# Review_PCD_1_1.net
KiCad netlist of a schematic drawn in EAGLE
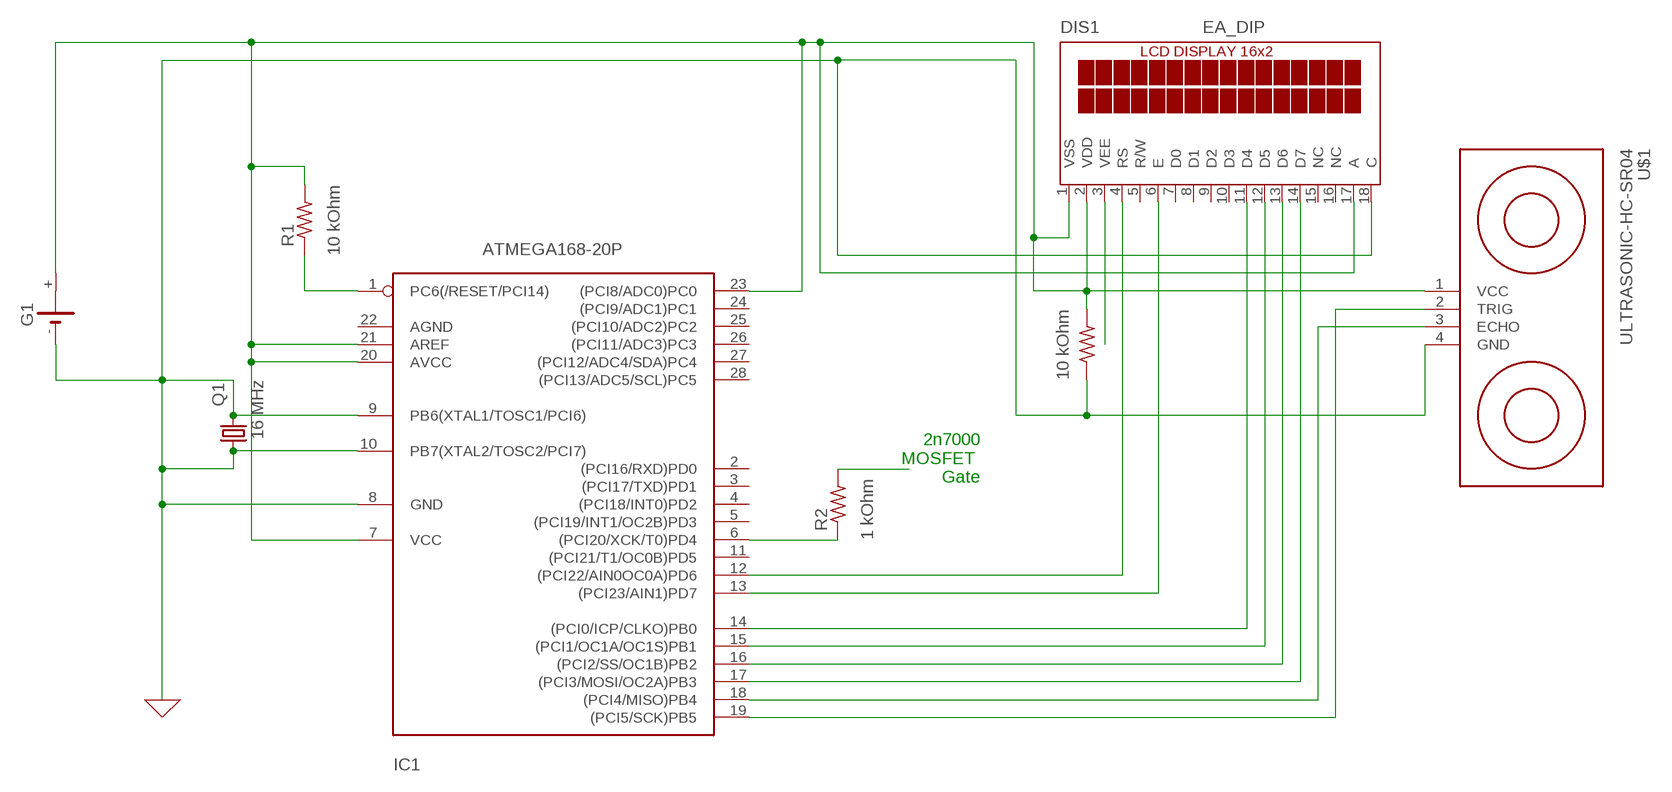
[diagram p0: schematic, sheet 1]

(export (version "E")
  (design (tool "Eeschema 10.0.6"))
  (components
    (comp (ref "DIS1")
      (value "EA_DIP")
      (footprint "eagle-import:EA_DIP")
      (libsource (lib "eagle-import") (part "EA_DIP"))
    )
    (comp (ref "G1")
      (value "CR1/2")
      (footprint "eagle-import:CR1_2")
      (libsource (lib "eagle-import") (part "CR1/2"))
    )
    (comp (ref "IC1")
      (value "ATMEGA168-20P")
      (footprint "eagle-import:DIL28-3")
      (libsource (lib "eagle-import") (part "ATMEGA168P-20"))
    )
    (comp (ref "Q1")
      (value "KX-4")
      (footprint "eagle-import:1.6X1.2")
      (fields (field (name "Q1") "16 MHz"))
      (libsource (lib "eagle-import") (part "KX-4"))
    )
    (comp (ref "R1")
      (value "R-US_R2012W")
      (footprint "eagle-import:R2012W")
      (fields (field (name "R1") "10 kOhm"))
      (libsource (lib "eagle-import") (part "R-US_R2012W"))
    )
    (comp (ref "R2")
      (value "R-US_R2012W")
      (footprint "eagle-import:R2012W")
      (fields (field (name "R1") "1 kOhm"))
      (libsource (lib "eagle-import") (part "R-US_R2012W"))
    )
    (comp (ref "R3")
      (value "R-US_R2012W")
      (footprint "eagle-import:R2012W")
      (fields (field (name "R1") "10 kOhm"))
      (libsource (lib "eagle-import") (part "R-US_R2012W"))
    )
    (comp (ref "U$1")
      (value "ULTRASONIC-HC-SR04")
      (footprint "eagle-import:ULTRASONIC-HC-SR04")
      (libsource (lib "eagle-import") (part "ULTRASONIC-HC-SR04"))
    )
  )
  (nets
    (net (code "1") (name "GND") (class "Default")
      (node (ref "DIS1") (pin "18") (pinfunction "C_18") (pintype "passive"))
      (node (ref "G1") (pin "-") (pinfunction "-_-") (pintype "passive"))
      (node (ref "IC1") (pin "10") (pinfunction "PB7(XTAL2/TOSC2/PCI7)_10") (pintype "bidirectional"))
      (node (ref "IC1") (pin "8") (pinfunction "GND_8") (pintype "bidirectional"))
      (node (ref "IC1") (pin "9") (pinfunction "PB6(XTAL1/TOSC1/PCI6)_9") (pintype "bidirectional"))
      (node (ref "Q1") (pin "1") (pinfunction "1_1") (pintype "passive"))
      (node (ref "Q1") (pin "3") (pinfunction "2_3") (pintype "passive"))
      (node (ref "R3") (pin "1") (pinfunction "1_1") (pintype "passive"))
      (node (ref "U$1") (pin "4") (pinfunction "GND_4") (pintype "power_in"))
    )
    (net (code "2") (name "Net-(DIS1-A)") (class "Default")
      (node (ref "DIS1") (pin "1") (pinfunction "VSS_1") (pintype "power_in"))
      (node (ref "DIS1") (pin "17") (pinfunction "A_17") (pintype "passive"))
      (node (ref "DIS1") (pin "2") (pinfunction "VDD_2") (pintype "power_in"))
      (node (ref "G1") (pin "+") (pinfunction "+_+") (pintype "passive"))
      (node (ref "IC1") (pin "20") (pinfunction "AVCC_20") (pintype "bidirectional"))
      (node (ref "IC1") (pin "21") (pinfunction "AREF_21") (pintype "bidirectional"))
      (node (ref "IC1") (pin "23") (pinfunction "(PCI8/ADC0)PC0_23") (pintype "bidirectional"))
      (node (ref "IC1") (pin "7") (pinfunction "VCC_7") (pintype "bidirectional"))
      (node (ref "R1") (pin "2") (pinfunction "2_2") (pintype "passive"))
      (node (ref "R3") (pin "2") (pinfunction "2_2") (pintype "passive"))
      (node (ref "U$1") (pin "1") (pinfunction "VCC_1") (pintype "power_in"))
    )
    (net (code "3") (name "Net-(DIS1-D4)") (class "Default")
      (node (ref "DIS1") (pin "11") (pinfunction "D4_11") (pintype "input"))
      (node (ref "IC1") (pin "14") (pinfunction "(PCI0/ICP/CLKO)PB0_14") (pintype "bidirectional"))
    )
    (net (code "4") (name "Net-(DIS1-D5)") (class "Default")
      (node (ref "DIS1") (pin "12") (pinfunction "D5_12") (pintype "input"))
      (node (ref "IC1") (pin "15") (pinfunction "(PCI1/OC1A/OC1S)PB1_15") (pintype "bidirectional"))
    )
    (net (code "5") (name "Net-(DIS1-D6)") (class "Default")
      (node (ref "DIS1") (pin "13") (pinfunction "D6_13") (pintype "input"))
      (node (ref "IC1") (pin "16") (pinfunction "(PCI2/SS/OC1B)PB2_16") (pintype "bidirectional"))
    )
    (net (code "6") (name "Net-(DIS1-D7)") (class "Default")
      (node (ref "DIS1") (pin "14") (pinfunction "D7_14") (pintype "input"))
      (node (ref "IC1") (pin "17") (pinfunction "(PCI3/MOSI/OC2A)PB3_17") (pintype "bidirectional"))
    )
    (net (code "7") (name "Net-(DIS1-E)") (class "Default")
      (node (ref "DIS1") (pin "6") (pinfunction "E_6") (pintype "input"))
      (node (ref "IC1") (pin "13") (pinfunction "(PCI23/AIN1)PD7_13") (pintype "bidirectional"))
    )
    (net (code "8") (name "Net-(DIS1-RS)") (class "Default")
      (node (ref "DIS1") (pin "4") (pinfunction "RS_4") (pintype "input"))
      (node (ref "IC1") (pin "12") (pinfunction "(PCI22/AIN0OC0A)PD6_12") (pintype "bidirectional"))
    )
    (net (code "9") (name "Net-(IC1-(PCI4{slash}MISO)PB4)") (class "Default")
      (node (ref "IC1") (pin "18") (pinfunction "(PCI4/MISO)PB4_18") (pintype "bidirectional"))
      (node (ref "U$1") (pin "3") (pinfunction "ECHO_3") (pintype "output"))
    )
    (net (code "10") (name "Net-(IC1-(PCI5{slash}SCK)PB5)") (class "Default")
      (node (ref "IC1") (pin "19") (pinfunction "(PCI5/SCK)PB5_19") (pintype "bidirectional"))
      (node (ref "U$1") (pin "2") (pinfunction "TRIG_2") (pintype "input"))
    )
    (net (code "11") (name "Net-(IC1-(PCI20{slash}XCK{slash}T0)PD4)") (class "Default")
      (node (ref "IC1") (pin "6") (pinfunction "(PCI20/XCK/T0)PD4_6") (pintype "bidirectional"))
      (node (ref "R2") (pin "1") (pinfunction "1_1") (pintype "passive"))
    )
    (net (code "12") (name "Net-(IC1-PC6({slash}RESET{slash}PCI14))") (class "Default")
      (node (ref "IC1") (pin "1") (pinfunction "PC6(/RESET/PCI14)_1") (pintype "bidirectional"))
      (node (ref "R1") (pin "1") (pinfunction "1_1") (pintype "passive"))
    )
    (net (code "13") (name "unconnected-(DIS1-D0-Pad7)") (class "Default")
      (node (ref "DIS1") (pin "7") (pinfunction "D0_7") (pintype "input"))
    )
    (net (code "14") (name "unconnected-(DIS1-D1-Pad8)") (class "Default")
      (node (ref "DIS1") (pin "8") (pinfunction "D1_8") (pintype "input"))
    )
    (net (code "15") (name "unconnected-(DIS1-D2-Pad9)") (class "Default")
      (node (ref "DIS1") (pin "9") (pinfunction "D2_9") (pintype "input"))
    )
    (net (code "16") (name "unconnected-(DIS1-D3-Pad10)") (class "Default")
      (node (ref "DIS1") (pin "10") (pinfunction "D3_10") (pintype "input"))
    )
    (net (code "17") (name "unconnected-(DIS1-NC-Pad15)") (class "Default")
      (node (ref "DIS1") (pin "15") (pinfunction "NC_15") (pintype "no_connect"))
    )
    (net (code "18") (name "unconnected-(DIS1-NC-Pad16)") (class "Default")
      (node (ref "DIS1") (pin "16") (pinfunction "NC_16") (pintype "no_connect"))
    )
    (net (code "19") (name "unconnected-(DIS1-R{slash}W-Pad5)") (class "Default")
      (node (ref "DIS1") (pin "5") (pinfunction "R/W_5") (pintype "input"))
    )
    (net (code "20") (name "unconnected-(DIS1-VEE-Pad3)") (class "Default")
      (node (ref "DIS1") (pin "3") (pinfunction "VEE_3") (pintype "power_in"))
    )
    (net (code "21") (name "unconnected-(G1-+-Pad+@1)") (class "Default")
      (node (ref "G1") (pin "+@1") (pinfunction "+_+@1") (pintype "passive"))
    )
    (net (code "22") (name "unconnected-(IC1-(PCI9{slash}ADC1)PC1-Pad24)") (class "Default")
      (node (ref "IC1") (pin "24") (pinfunction "(PCI9/ADC1)PC1_24") (pintype "bidirectional"))
    )
    (net (code "23") (name "unconnected-(IC1-(PCI10{slash}ADC2)PC2-Pad25)") (class "Default")
      (node (ref "IC1") (pin "25") (pinfunction "(PCI10/ADC2)PC2_25") (pintype "bidirectional"))
    )
    (net (code "24") (name "unconnected-(IC1-(PCI11{slash}ADC3)PC3-Pad26)") (class "Default")
      (node (ref "IC1") (pin "26") (pinfunction "(PCI11/ADC3)PC3_26") (pintype "bidirectional"))
    )
    (net (code "25") (name "unconnected-(IC1-(PCI12{slash}ADC4{slash}SDA)PC4-Pad27)") (class "Default")
      (node (ref "IC1") (pin "27") (pinfunction "(PCI12/ADC4/SDA)PC4_27") (pintype "bidirectional"))
    )
    (net (code "26") (name "unconnected-(IC1-(PCI13{slash}ADC5{slash}SCL)PC5-Pad28)") (class "Default")
      (node (ref "IC1") (pin "28") (pinfunction "(PCI13/ADC5/SCL)PC5_28") (pintype "bidirectional"))
    )
    (net (code "27") (name "unconnected-(IC1-(PCI16{slash}RXD)PD0-Pad2)") (class "Default")
      (node (ref "IC1") (pin "2") (pinfunction "(PCI16/RXD)PD0_2") (pintype "bidirectional"))
    )
    (net (code "28") (name "unconnected-(IC1-(PCI17{slash}TXD)PD1-Pad3)") (class "Default")
      (node (ref "IC1") (pin "3") (pinfunction "(PCI17/TXD)PD1_3") (pintype "bidirectional"))
    )
    (net (code "29") (name "unconnected-(IC1-(PCI18{slash}INT0)PD2-Pad4)") (class "Default")
      (node (ref "IC1") (pin "4") (pinfunction "(PCI18/INT0)PD2_4") (pintype "bidirectional"))
    )
    (net (code "30") (name "unconnected-(IC1-(PCI19{slash}INT1{slash}OC2B)PD3-Pad5)") (class "Default")
      (node (ref "IC1") (pin "5") (pinfunction "(PCI19/INT1/OC2B)PD3_5") (pintype "bidirectional"))
    )
    (net (code "31") (name "unconnected-(IC1-(PCI21{slash}T1{slash}OC0B)PD5-Pad11)") (class "Default")
      (node (ref "IC1") (pin "11") (pinfunction "(PCI21/T1/OC0B)PD5_11") (pintype "bidirectional"))
    )
    (net (code "32") (name "unconnected-(IC1-AGND-Pad22)") (class "Default")
      (node (ref "IC1") (pin "22") (pinfunction "AGND_22") (pintype "bidirectional"))
    )
    (net (code "33") (name "unconnected-(R2-Pad2)") (class "Default")
      (node (ref "R2") (pin "2") (pinfunction "2_2") (pintype "passive"))
    )
  )
)
